# RegisterB.net
KiCad netlist of a schematic drawn in Altium Designer
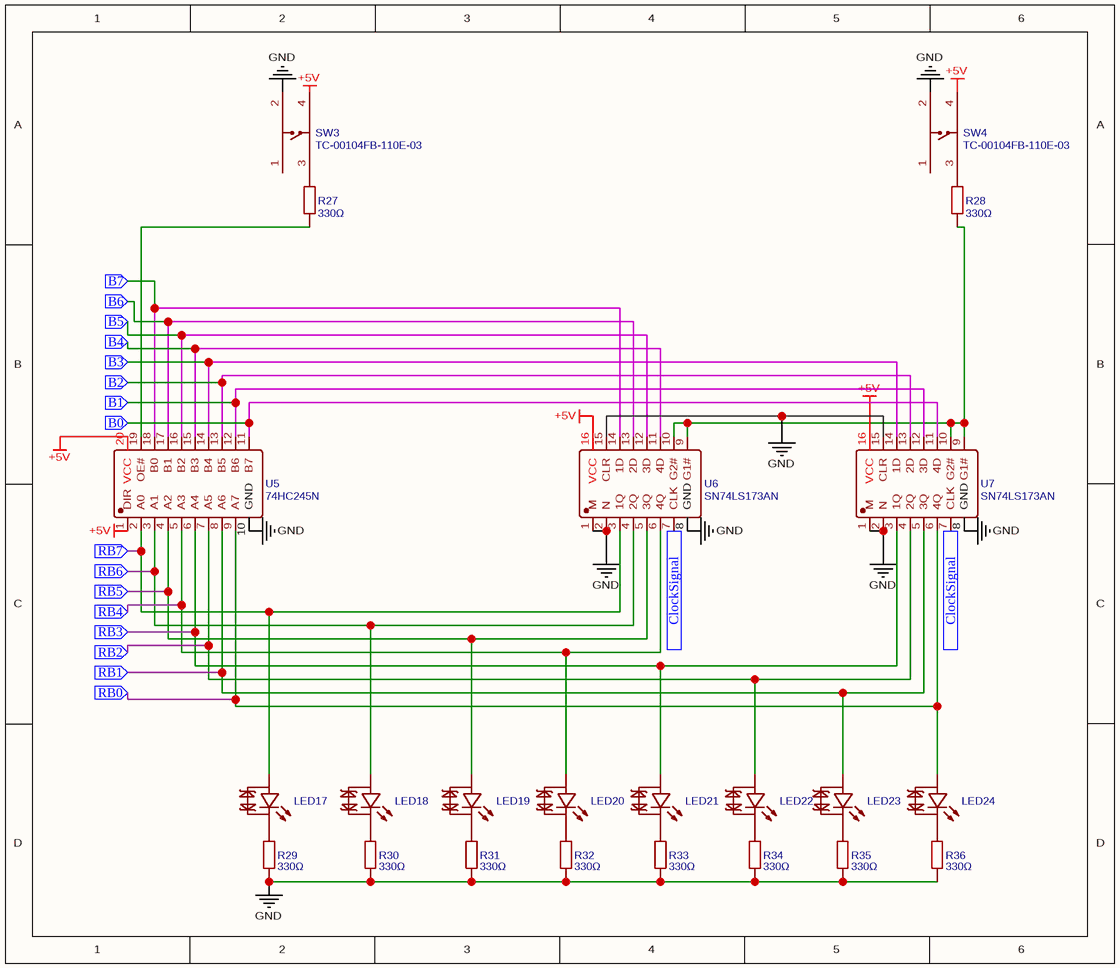
[diagram p0: RegisterB.schdoc]

(export (version "E")
  (design (tool "Eeschema 10.0.6"))
  (components
    (comp (ref "LED17")
      (value "204-15UTC/S400-X9-L")
      (fields (field (name "MANUFACTURER") "EVERLIGHT(亿光)") (field (name "CONTRIBUTOR") "LCSC"))
      (libsource (lib "altium-import") (part "root_3_204-15UTC/S400-X9-L_"))
    )
    (comp (ref "LED18")
      (value "204-15UTC/S400-X9-L")
      (fields (field (name "MANUFACTURER") "EVERLIGHT(亿光)") (field (name "CONTRIBUTOR") "LCSC"))
      (libsource (lib "altium-import") (part "root_3_204-15UTC/S400-X9-L_"))
    )
    (comp (ref "LED19")
      (value "204-15UTC/S400-X9-L")
      (fields (field (name "MANUFACTURER") "EVERLIGHT(亿光)") (field (name "CONTRIBUTOR") "LCSC"))
      (libsource (lib "altium-import") (part "root_3_204-15UTC/S400-X9-L_"))
    )
    (comp (ref "LED20")
      (value "204-15UTC/S400-X9-L")
      (fields (field (name "MANUFACTURER") "EVERLIGHT(亿光)") (field (name "CONTRIBUTOR") "LCSC"))
      (libsource (lib "altium-import") (part "root_3_204-15UTC/S400-X9-L_"))
    )
    (comp (ref "LED21")
      (value "204-15UTC/S400-X9-L")
      (fields (field (name "MANUFACTURER") "EVERLIGHT(亿光)") (field (name "CONTRIBUTOR") "LCSC"))
      (libsource (lib "altium-import") (part "root_3_204-15UTC/S400-X9-L_"))
    )
    (comp (ref "LED22")
      (value "204-15UTC/S400-X9-L")
      (fields (field (name "MANUFACTURER") "EVERLIGHT(亿光)") (field (name "CONTRIBUTOR") "LCSC"))
      (libsource (lib "altium-import") (part "root_3_204-15UTC/S400-X9-L_"))
    )
    (comp (ref "LED23")
      (value "204-15UTC/S400-X9-L")
      (fields (field (name "MANUFACTURER") "EVERLIGHT(亿光)") (field (name "CONTRIBUTOR") "LCSC"))
      (libsource (lib "altium-import") (part "root_3_204-15UTC/S400-X9-L_"))
    )
    (comp (ref "LED24")
      (value "204-15UTC/S400-X9-L")
      (fields (field (name "MANUFACTURER") "EVERLIGHT(亿光)") (field (name "CONTRIBUTOR") "LCSC"))
      (libsource (lib "altium-import") (part "root_3_204-15UTC/S400-X9-L_"))
    )
    (comp (ref "R27")
      (value "330Ω")
      (fields
        (field (name "MANUFACTURER") "CCO(千志电子)")
        (field (name "MANUFACTURER PART") "MF1/2W-0.1Ω±1% T")
        (field (name "CONTRIBUTOR") "LCSC")
      )
      (libsource (lib "altium-import") (part "root_1_330Ω_"))
    )
    (comp (ref "R28")
      (value "330Ω")
      (fields
        (field (name "MANUFACTURER") "CCO(千志电子)")
        (field (name "MANUFACTURER PART") "MF1/2W-0.1Ω±1% T")
        (field (name "CONTRIBUTOR") "LCSC")
      )
      (libsource (lib "altium-import") (part "root_1_330Ω_"))
    )
    (comp (ref "R29")
      (value "330Ω")
      (fields
        (field (name "MANUFACTURER") "CCO(千志电子)")
        (field (name "MANUFACTURER PART") "MF1/2W-0.1Ω±1% T")
        (field (name "CONTRIBUTOR") "LCSC")
      )
      (libsource (lib "altium-import") (part "root_3_330Ω_"))
    )
    (comp (ref "R30")
      (value "330Ω")
      (fields
        (field (name "MANUFACTURER") "CCO(千志电子)")
        (field (name "MANUFACTURER PART") "MF1/2W-0.1Ω±1% T")
        (field (name "CONTRIBUTOR") "LCSC")
      )
      (libsource (lib "altium-import") (part "root_3_330Ω_"))
    )
    (comp (ref "R31")
      (value "330Ω")
      (fields
        (field (name "MANUFACTURER") "CCO(千志电子)")
        (field (name "MANUFACTURER PART") "MF1/2W-0.1Ω±1% T")
        (field (name "CONTRIBUTOR") "LCSC")
      )
      (libsource (lib "altium-import") (part "root_3_330Ω_"))
    )
    (comp (ref "R32")
      (value "330Ω")
      (fields
        (field (name "MANUFACTURER") "CCO(千志电子)")
        (field (name "MANUFACTURER PART") "MF1/2W-0.1Ω±1% T")
        (field (name "CONTRIBUTOR") "LCSC")
      )
      (libsource (lib "altium-import") (part "root_3_330Ω_"))
    )
    (comp (ref "R33")
      (value "330Ω")
      (fields
        (field (name "MANUFACTURER") "CCO(千志电子)")
        (field (name "MANUFACTURER PART") "MF1/2W-0.1Ω±1% T")
        (field (name "CONTRIBUTOR") "LCSC")
      )
      (libsource (lib "altium-import") (part "root_3_330Ω_"))
    )
    (comp (ref "R34")
      (value "330Ω")
      (fields
        (field (name "MANUFACTURER") "CCO(千志电子)")
        (field (name "MANUFACTURER PART") "MF1/2W-0.1Ω±1% T")
        (field (name "CONTRIBUTOR") "LCSC")
      )
      (libsource (lib "altium-import") (part "root_3_330Ω_"))
    )
    (comp (ref "R35")
      (value "330Ω")
      (fields
        (field (name "MANUFACTURER") "CCO(千志电子)")
        (field (name "MANUFACTURER PART") "MF1/2W-0.1Ω±1% T")
        (field (name "CONTRIBUTOR") "LCSC")
      )
      (libsource (lib "altium-import") (part "root_3_330Ω_"))
    )
    (comp (ref "R36")
      (value "330Ω")
      (fields
        (field (name "MANUFACTURER") "CCO(千志电子)")
        (field (name "MANUFACTURER PART") "MF1/2W-0.1Ω±1% T")
        (field (name "CONTRIBUTOR") "LCSC")
      )
      (libsource (lib "altium-import") (part "root_3_330Ω_"))
    )
    (comp (ref "SW3")
      (value "TC-00104FB-110E-03")
      (fields (field (name "MANUFACTURER") "HOOYA(皓宇电子)") (field (name "CONTRIBUTOR") "lcsc"))
      (libsource (lib "altium-import") (part "root_1_TC-00104FB-110E-03_"))
    )
    (comp (ref "SW4")
      (value "TC-00104FB-110E-03")
      (fields (field (name "MANUFACTURER") "HOOYA(皓宇电子)") (field (name "CONTRIBUTOR") "lcsc"))
      (libsource (lib "altium-import") (part "root_1_TC-00104FB-110E-03_"))
    )
    (comp (ref "U5")
      (value "74HC245N")
      (fields (field (name "MANUFACTURER") "HGSEMI(华冠)") (field (name "CONTRIBUTOR") "LCSC"))
      (libsource (lib "altium-import") (part "root_1_74HC245N_"))
    )
    (comp (ref "U6")
      (value "SN74LS173AN")
      (fields (field (name "MANUFACTURER") "TI(德州仪器)") (field (name "CONTRIBUTOR") "LCSC"))
      (libsource (lib "altium-import") (part "root_1_SN74LS173AN_"))
    )
    (comp (ref "U7")
      (value "SN74LS173AN")
      (fields (field (name "MANUFACTURER") "TI(德州仪器)") (field (name "CONTRIBUTOR") "LCSC"))
      (libsource (lib "altium-import") (part "root_1_SN74LS173AN_"))
    )
  )
  (nets
    (net (code "1") (name "+5V") (class "Default")
      (node (ref "SW4") (pin "4") (pinfunction "4_4") (pintype "passive"))
      (node (ref "U5") (pin "1") (pinfunction "DIR_1") (pintype "passive"))
      (node (ref "U5") (pin "20") (pinfunction "VCC_20") (pintype "passive"))
      (node (ref "U6") (pin "16") (pinfunction "VCC_16") (pintype "passive"))
      (node (ref "U7") (pin "16") (pinfunction "VCC_16") (pintype "passive"))
    )
    (net (code "2") (name "/B0") (class "Default")
      (node (ref "U5") (pin "11") (pinfunction "B7_11") (pintype "passive"))
      (node (ref "U7") (pin "11") (pinfunction "4D_11") (pintype "passive"))
    )
    (net (code "3") (name "/B1") (class "Default")
      (node (ref "U5") (pin "12") (pinfunction "B6_12") (pintype "passive"))
      (node (ref "U7") (pin "12") (pinfunction "3D_12") (pintype "passive"))
    )
    (net (code "4") (name "/B2") (class "Default")
      (node (ref "U5") (pin "13") (pinfunction "B5_13") (pintype "passive"))
      (node (ref "U7") (pin "13") (pinfunction "2D_13") (pintype "passive"))
    )
    (net (code "5") (name "/B3") (class "Default")
      (node (ref "U5") (pin "14") (pinfunction "B4_14") (pintype "passive"))
      (node (ref "U7") (pin "14") (pinfunction "1D_14") (pintype "passive"))
    )
    (net (code "6") (name "/B4") (class "Default")
      (node (ref "U5") (pin "15") (pinfunction "B3_15") (pintype "passive"))
      (node (ref "U6") (pin "11") (pinfunction "4D_11") (pintype "passive"))
    )
    (net (code "7") (name "/B5") (class "Default")
      (node (ref "U5") (pin "16") (pinfunction "B2_16") (pintype "passive"))
      (node (ref "U6") (pin "12") (pinfunction "3D_12") (pintype "passive"))
    )
    (net (code "8") (name "/B6") (class "Default")
      (node (ref "U5") (pin "17") (pinfunction "B1_17") (pintype "passive"))
      (node (ref "U6") (pin "13") (pinfunction "2D_13") (pintype "passive"))
    )
    (net (code "9") (name "/B7") (class "Default")
      (node (ref "U5") (pin "18") (pinfunction "B0_18") (pintype "passive"))
      (node (ref "U6") (pin "14") (pinfunction "1D_14") (pintype "passive"))
    )
    (net (code "10") (name "/ClockSignal") (class "Default")
      (node (ref "U6") (pin "7") (pinfunction "CLK_7") (pintype "passive"))
      (node (ref "U7") (pin "7") (pinfunction "CLK_7") (pintype "passive"))
    )
    (net (code "11") (name "/RB0") (class "Default")
      (node (ref "LED24") (pin "1") (pinfunction "A_1") (pintype "passive"))
      (node (ref "U5") (pin "9") (pinfunction "A7_9") (pintype "passive"))
      (node (ref "U7") (pin "6") (pinfunction "4Q_6") (pintype "passive"))
    )
    (net (code "12") (name "/RB1") (class "Default")
      (node (ref "LED23") (pin "1") (pinfunction "A_1") (pintype "passive"))
      (node (ref "U5") (pin "8") (pinfunction "A6_8") (pintype "passive"))
      (node (ref "U7") (pin "5") (pinfunction "3Q_5") (pintype "passive"))
    )
    (net (code "13") (name "/RB2") (class "Default")
      (node (ref "LED22") (pin "1") (pinfunction "A_1") (pintype "passive"))
      (node (ref "U5") (pin "7") (pinfunction "A5_7") (pintype "passive"))
      (node (ref "U7") (pin "4") (pinfunction "2Q_4") (pintype "passive"))
    )
    (net (code "14") (name "/RB3") (class "Default")
      (node (ref "LED21") (pin "1") (pinfunction "A_1") (pintype "passive"))
      (node (ref "U5") (pin "6") (pinfunction "A4_6") (pintype "passive"))
      (node (ref "U7") (pin "3") (pinfunction "1Q_3") (pintype "passive"))
    )
    (net (code "15") (name "/RB4") (class "Default")
      (node (ref "LED20") (pin "1") (pinfunction "A_1") (pintype "passive"))
      (node (ref "U5") (pin "5") (pinfunction "A3_5") (pintype "passive"))
      (node (ref "U6") (pin "6") (pinfunction "4Q_6") (pintype "passive"))
    )
    (net (code "16") (name "/RB5") (class "Default")
      (node (ref "LED19") (pin "1") (pinfunction "A_1") (pintype "passive"))
      (node (ref "U5") (pin "4") (pinfunction "A2_4") (pintype "passive"))
      (node (ref "U6") (pin "5") (pinfunction "3Q_5") (pintype "passive"))
    )
    (net (code "17") (name "/RB6") (class "Default")
      (node (ref "LED18") (pin "1") (pinfunction "A_1") (pintype "passive"))
      (node (ref "U5") (pin "3") (pinfunction "A1_3") (pintype "passive"))
      (node (ref "U6") (pin "4") (pinfunction "2Q_4") (pintype "passive"))
    )
    (net (code "18") (name "/RB7") (class "Default")
      (node (ref "LED17") (pin "1") (pinfunction "A_1") (pintype "passive"))
      (node (ref "U5") (pin "2") (pinfunction "A0_2") (pintype "passive"))
      (node (ref "U6") (pin "3") (pinfunction "1Q_3") (pintype "passive"))
    )
    (net (code "19") (name "GND") (class "Default")
      (node (ref "R29") (pin "2") (pinfunction "2_2") (pintype "passive"))
      (node (ref "R30") (pin "2") (pinfunction "2_2") (pintype "passive"))
      (node (ref "R31") (pin "2") (pinfunction "2_2") (pintype "passive"))
      (node (ref "R32") (pin "2") (pinfunction "2_2") (pintype "passive"))
      (node (ref "R33") (pin "2") (pinfunction "2_2") (pintype "passive"))
      (node (ref "R34") (pin "2") (pinfunction "2_2") (pintype "passive"))
      (node (ref "R35") (pin "2") (pinfunction "2_2") (pintype "passive"))
      (node (ref "R36") (pin "2") (pinfunction "2_2") (pintype "passive"))
      (node (ref "SW3") (pin "2") (pinfunction "2_2") (pintype "passive"))
      (node (ref "SW4") (pin "2") (pinfunction "2_2") (pintype "passive"))
      (node (ref "U5") (pin "10") (pinfunction "GND_10") (pintype "passive"))
      (node (ref "U6") (pin "1") (pinfunction "M_1") (pintype "passive"))
      (node (ref "U6") (pin "15") (pinfunction "CLR_15") (pintype "passive"))
      (node (ref "U6") (pin "2") (pinfunction "N_2") (pintype "passive"))
      (node (ref "U6") (pin "8") (pinfunction "GND_8") (pintype "passive"))
      (node (ref "U7") (pin "1") (pinfunction "M_1") (pintype "passive"))
      (node (ref "U7") (pin "15") (pinfunction "CLR_15") (pintype "passive"))
      (node (ref "U7") (pin "2") (pinfunction "N_2") (pintype "passive"))
      (node (ref "U7") (pin "8") (pinfunction "GND_8") (pintype "passive"))
    )
    (net (code "20") (name "Net-(LED17-C)") (class "Default")
      (node (ref "LED17") (pin "2") (pinfunction "C_2") (pintype "passive"))
      (node (ref "R29") (pin "1") (pinfunction "1_1") (pintype "passive"))
    )
    (net (code "21") (name "Net-(LED18-C)") (class "Default")
      (node (ref "LED18") (pin "2") (pinfunction "C_2") (pintype "passive"))
      (node (ref "R30") (pin "1") (pinfunction "1_1") (pintype "passive"))
    )
    (net (code "22") (name "Net-(LED19-C)") (class "Default")
      (node (ref "LED19") (pin "2") (pinfunction "C_2") (pintype "passive"))
      (node (ref "R31") (pin "1") (pinfunction "1_1") (pintype "passive"))
    )
    (net (code "23") (name "Net-(LED20-C)") (class "Default")
      (node (ref "LED20") (pin "2") (pinfunction "C_2") (pintype "passive"))
      (node (ref "R32") (pin "1") (pinfunction "1_1") (pintype "passive"))
    )
    (net (code "24") (name "Net-(LED21-C)") (class "Default")
      (node (ref "LED21") (pin "2") (pinfunction "C_2") (pintype "passive"))
      (node (ref "R33") (pin "1") (pinfunction "1_1") (pintype "passive"))
    )
    (net (code "25") (name "Net-(LED22-C)") (class "Default")
      (node (ref "LED22") (pin "2") (pinfunction "C_2") (pintype "passive"))
      (node (ref "R34") (pin "1") (pinfunction "1_1") (pintype "passive"))
    )
    (net (code "26") (name "Net-(LED23-C)") (class "Default")
      (node (ref "LED23") (pin "2") (pinfunction "C_2") (pintype "passive"))
      (node (ref "R35") (pin "1") (pinfunction "1_1") (pintype "passive"))
    )
    (net (code "27") (name "Net-(LED24-C)") (class "Default")
      (node (ref "LED24") (pin "2") (pinfunction "C_2") (pintype "passive"))
      (node (ref "R36") (pin "1") (pinfunction "1_1") (pintype "passive"))
    )
    (net (code "28") (name "Net-(R27-Pad2)") (class "Default")
      (node (ref "R27") (pin "2") (pinfunction "2_2") (pintype "passive"))
      (node (ref "SW3") (pin "3") (pinfunction "3_3") (pintype "passive"))
    )
    (net (code "29") (name "Net-(R28-Pad2)") (class "Default")
      (node (ref "R28") (pin "2") (pinfunction "2_2") (pintype "passive"))
      (node (ref "SW4") (pin "3") (pinfunction "3_3") (pintype "passive"))
    )
    (net (code "30") (name "Net-(U5-OE#)") (class "Default")
      (node (ref "R27") (pin "1") (pinfunction "1_1") (pintype "passive"))
      (node (ref "U5") (pin "19") (pinfunction "OE#_19") (pintype "passive"))
    )
    (net (code "31") (name "Net-(U6-G1#)") (class "Default")
      (node (ref "R28") (pin "1") (pinfunction "1_1") (pintype "passive"))
      (node (ref "U6") (pin "10") (pinfunction "G2#_10") (pintype "passive"))
      (node (ref "U6") (pin "9") (pinfunction "G1#_9") (pintype "passive"))
      (node (ref "U7") (pin "10") (pinfunction "G2#_10") (pintype "passive"))
      (node (ref "U7") (pin "9") (pinfunction "G1#_9") (pintype "passive"))
    )
    (net (code "32") (name "unconnected-(SW3-Pad1)") (class "Default")
      (node (ref "SW3") (pin "1") (pinfunction "1_1") (pintype "passive"))
    )
    (net (code "33") (name "unconnected-(SW3-Pad4)") (class "Default")
      (node (ref "SW3") (pin "4") (pinfunction "4_4") (pintype "passive"))
    )
    (net (code "34") (name "unconnected-(SW4-Pad1)") (class "Default")
      (node (ref "SW4") (pin "1") (pinfunction "1_1") (pintype "passive"))
    )
  )
)
